# ARM_PCB.net
KiCad netlist of a schematic drawn in Altium Designer
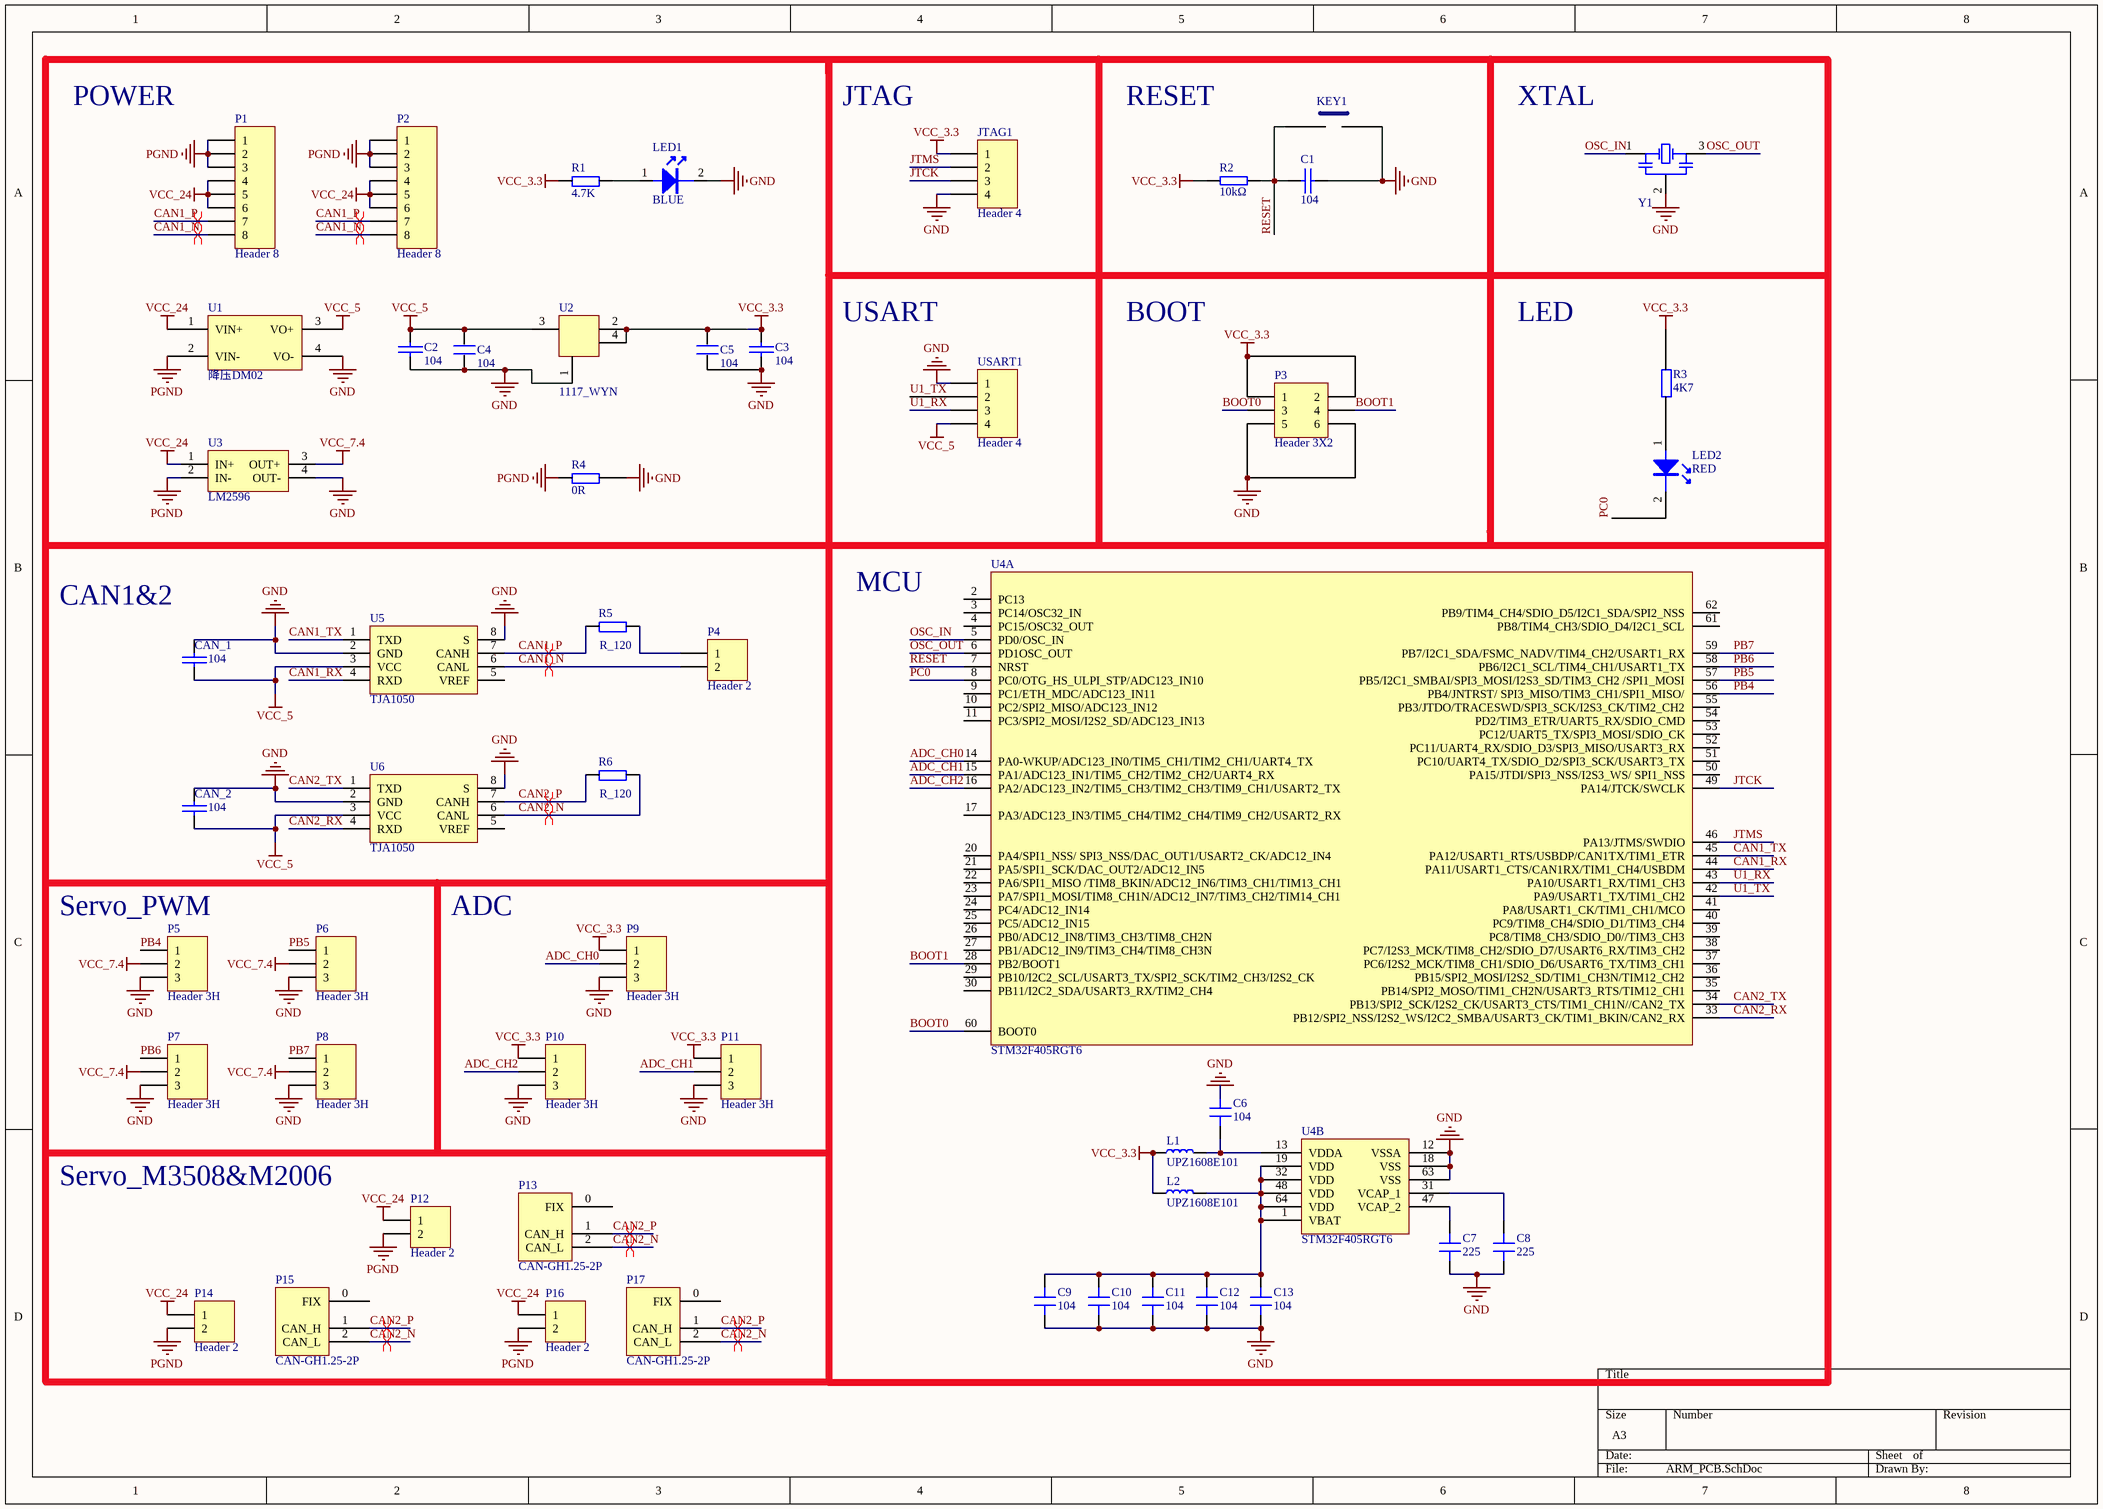
[diagram p0: ARM_PCB.SchDoc]

(export (version "E")
  (design (tool "Eeschema 10.0.6"))
  (components
    (comp (ref "C1") (value "104") (footprint "C0603") (libsource (lib "main") (part "C0603")))
    (comp (ref "C2") (value "104") (footprint "C0603") (libsource (lib "main") (part "C0603")))
    (comp (ref "C3") (value "104") (footprint "C0603") (libsource (lib "main") (part "C0603")))
    (comp (ref "C4") (value "104") (footprint "C0603") (libsource (lib "Rescue") (part "Cap")))
    (comp (ref "C5") (value "104") (footprint "C0603") (libsource (lib "Rescue") (part "Cap")))
    (comp (ref "C6")
      (value "104")
      (footprint "C0603/1608")
      (description "陶瓷电容")
      (libsource (lib "WMJ2019_Devices") (part "陶瓷电容"))
    )
    (comp (ref "C7")
      (value "225")
      (footprint "C0603/1608")
      (description "陶瓷电容")
      (libsource (lib "WMJ2019_Devices") (part "陶瓷电容"))
    )
    (comp (ref "C8")
      (value "225")
      (footprint "C0603/1608")
      (description "陶瓷电容")
      (libsource (lib "WMJ2019_Devices") (part "陶瓷电容"))
    )
    (comp (ref "C9")
      (value "104")
      (footprint "C0603/1608")
      (description "陶瓷电容")
      (libsource (lib "WMJ2019_Devices") (part "陶瓷电容"))
    )
    (comp (ref "C10")
      (value "104")
      (footprint "C0603/1608")
      (description "陶瓷电容")
      (libsource (lib "WMJ2019_Devices") (part "陶瓷电容"))
    )
    (comp (ref "C11")
      (value "104")
      (footprint "C0603/1608")
      (description "陶瓷电容")
      (libsource (lib "WMJ2019_Devices") (part "陶瓷电容"))
    )
    (comp (ref "C12")
      (value "104")
      (footprint "C0603/1608")
      (description "陶瓷电容")
      (libsource (lib "WMJ2019_Devices") (part "陶瓷电容"))
    )
    (comp (ref "C13")
      (value "104")
      (footprint "C0603/1608")
      (description "陶瓷电容")
      (libsource (lib "WMJ2019_Devices") (part "陶瓷电容"))
    )
    (comp (ref "CAN_1") (value "104") (footprint "C0603") (libsource (lib "STM32主处理板") (part "C0603")))
    (comp (ref "CAN_2") (value "104") (footprint "C0603") (libsource (lib "STM32主处理板") (part "C0603")))
    (comp (ref "JTAG1")
      (value "Header 4")
      (footprint "Header1*4_XH2.54_zhi")
      (description "Header, 4-Pin")
      (fields (field (name "PUBLISHER") "Altium Limited"))
      (libsource (lib "Miscellaneous Connectors") (part "Header 4"))
    )
    (comp (ref "KEY1") (value "KEY2") (footprint "KEY_RESET") (libsource (lib "library-1") (part "KEY")))
    (comp (ref "L1")
      (value "UPZ1608E101")
      (footprint "L0603/1608")
      (description "贴片磁珠")
      (libsource (lib "WMJ2019_Devices") (part "磁珠"))
    )
    (comp (ref "L2")
      (value "UPZ1608E101")
      (footprint "L0603/1608")
      (description "贴片磁珠")
      (libsource (lib "WMJ2019_Devices") (part "磁珠"))
    )
    (comp (ref "LED1")
      (value "LED BLUE")
      (footprint "LED0603")
      (fields (field (name "COLOR") "BLUE"))
      (libsource (lib "Rescue") (part "LED"))
    )
    (comp (ref "LED2")
      (value "LED RED")
      (footprint "LED0603")
      (fields (field (name "COLOR") "RED"))
      (libsource (lib "Rescue") (part "LED"))
    )
    (comp (ref "P1")
      (value "Header 8")
      (footprint "Header1*8_XH2.54_zhi")
      (description "Header, 8-Pin")
      (fields (field (name "PUBLISHER") "Altium Limited"))
      (libsource (lib "Miscellaneous Connectors") (part "Header 8"))
    )
    (comp (ref "P2")
      (value "Header 8")
      (footprint "Header1*8_XH2.54_zhi")
      (description "Header, 8-Pin")
      (fields (field (name "PUBLISHER") "Altium Limited"))
      (libsource (lib "Miscellaneous Connectors") (part "Header 8"))
    )
    (comp (ref "P3")
      (value "Header 3X2")
      (footprint "BOOT")
      (description "Header, 3-Pin, Dual row")
      (fields (field (name "PUBLISHER") "Altium Limited"))
      (libsource (lib "PCB_Project") (part "Header 3X2"))
    )
    (comp (ref "P4") (value "Header 2") (footprint "TM") (libsource (lib "Rescue") (part "Header 2")))
    (comp (ref "P5")
      (value "Header 3H")
      (footprint "Header1*3XH2.54")
      (libsource (lib "Rescue") (part "Header 3H"))
    )
    (comp (ref "P6")
      (value "Header 3H")
      (footprint "Header1*3XH2.54")
      (libsource (lib "Rescue") (part "Header 3H"))
    )
    (comp (ref "P7")
      (value "Header 3H")
      (footprint "Header1*3XH2.54")
      (libsource (lib "Rescue") (part "Header 3H"))
    )
    (comp (ref "P8")
      (value "Header 3H")
      (footprint "Header1*3XH2.54")
      (libsource (lib "Rescue") (part "Header 3H"))
    )
    (comp (ref "P9")
      (value "Header 3H")
      (footprint "Header1*3XH2.54")
      (libsource (lib "Rescue") (part "Header 3H"))
    )
    (comp (ref "P10")
      (value "Header 3H")
      (footprint "Header1*3XH2.54")
      (libsource (lib "Rescue") (part "Header 3H"))
    )
    (comp (ref "P11")
      (value "Header 3H")
      (footprint "Header1*3XH2.54")
      (libsource (lib "Rescue") (part "Header 3H"))
    )
    (comp (ref "P12") (value "Header 2") (footprint "XT30_母") (libsource (lib "Rescue") (part "Header 2")))
    (comp (ref "P13")
      (value "CAN-GH1.25-2P")
      (footprint "GH1.25-2P（立式）")
      (description "CAN-GH1.25-2P端子座")
      (libsource (lib "PCB_Project1") (part "CAN-GH1.25-2P"))
    )
    (comp (ref "P14") (value "Header 2") (footprint "XT30_母") (libsource (lib "Rescue") (part "Header 2")))
    (comp (ref "P15")
      (value "CAN-GH1.25-2P")
      (footprint "GH1.25-2P（立式）")
      (description "CAN-GH1.25-2P端子座")
      (libsource (lib "PCB_Project1") (part "CAN-GH1.25-2P"))
    )
    (comp (ref "P16") (value "Header 2") (footprint "XT30_母") (libsource (lib "Rescue") (part "Header 2")))
    (comp (ref "P17")
      (value "CAN-GH1.25-2P")
      (footprint "GH1.25-2P（立式）")
      (description "CAN-GH1.25-2P端子座")
      (libsource (lib "PCB_Project1") (part "CAN-GH1.25-2P"))
    )
    (comp (ref "R1") (value "4.7K") (footprint "R0603") (libsource (lib "战舰STM32开发板底板封装库") (part "R")))
    (comp (ref "R2") (value "10kΩ") (footprint "R0603") (libsource (lib "main") (part "RES_WYN")))
    (comp (ref "R3") (value "4K7") (footprint "R0603") (libsource (lib "Rescue") (part "Resistor")))
    (comp (ref "R4") (value "0R") (footprint "R0603") (libsource (lib "Rescue") (part "Resistor")))
    (comp (ref "R5") (value "R_120") (footprint "R0603") (libsource (lib "战舰STM32开发板底板封装库") (part "R")))
    (comp (ref "R6") (value "R_120") (footprint "R0603") (libsource (lib "战舰STM32开发板底板封装库") (part "R")))
    (comp (ref "U1") (value "降压DM02") (footprint "降压DM02") (libsource (lib "Rescue") (part "降压DM02")))
    (comp (ref "U2") (value "1117_WYN") (footprint "SOT-223") (libsource (lib "STM32主处理板") (part "1117_WYN")))
    (comp (ref "U3")
      (value "LM2596")
      (footprint "LM2596_big")
      (description "云辉 LM2596S DC-DC降压电源模块")
      (libsource (lib "舞蹈常用原理图库") (part "DC-DC稳压模块"))
    )
    (comp (ref "U4")
      (value "STM32F405RGT6")
      (footprint "LQFP64")
      (description "微控制器STM32F405RGT6")
      (libsource (lib "WMJ2019_MCU") (part "STM32F405RGT6"))
    )
    (comp (ref "U5") (value "TJA1050") (footprint "SO8_M") (libsource (lib "Rescue") (part "TJA1050")))
    (comp (ref "U6") (value "TJA1050") (footprint "SO8_M") (libsource (lib "Rescue") (part "TJA1050")))
    (comp (ref "USART1")
      (value "Header 4")
      (footprint "Header1*4_XH2.54_zhi")
      (description "Header, 4-Pin")
      (fields (field (name "PUBLISHER") "Altium Limited"))
      (libsource (lib "Miscellaneous Connectors") (part "Header 4"))
    )
    (comp (ref "Y1")
      (value "Crystal_Cap")
      (footprint "XTAL-3213")
      (fields (field (name "PUBLISHER") "Altium Limited"))
      (libsource (lib "chassis_PCB_Project") (part "Crystal_Cap"))
    )
  )
  (nets
    (net (code "1") (name "/ADC_CH0") (class "Default")
      (node (ref "P9") (pin "2") (pinfunction "2_2") (pintype "passive"))
      (node (ref "U4") (pin "14") (pinfunction "PA0-WKUP/ADC123_IN0/TIM5_CH1/TIM2_CH1/UART4_TX_14") (pintype "passive"))
    )
    (net (code "2") (name "/ADC_CH1") (class "Default")
      (node (ref "P11") (pin "2") (pinfunction "2_2") (pintype "passive"))
      (node (ref "U4") (pin "15") (pinfunction "PA1/ADC123_IN1/TIM5_CH2/TIM2_CH2/UART4_RX_15") (pintype "passive"))
    )
    (net (code "3") (name "/ADC_CH2") (class "Default")
      (node (ref "P10") (pin "2") (pinfunction "2_2") (pintype "passive"))
      (node (ref "U4") (pin "16") (pinfunction "PA2/ADC123_IN2/TIM5_CH3/TIM2_CH3/TIM9_CH1/USART2_TX_16") (pintype "passive"))
    )
    (net (code "4") (name "/BOOT0") (class "Default")
      (node (ref "P3") (pin "3") (pinfunction "3_3") (pintype "passive"))
      (node (ref "U4") (pin "60") (pinfunction "BOOT0_60") (pintype "passive"))
    )
    (net (code "5") (name "/BOOT1") (class "Default")
      (node (ref "P3") (pin "4") (pinfunction "4_4") (pintype "passive"))
      (node (ref "U4") (pin "28") (pinfunction "PB2/BOOT1_28") (pintype "passive"))
    )
    (net (code "6") (name "/CAN1_N") (class "Default")
      (node (ref "P1") (pin "8") (pinfunction "8_8") (pintype "passive"))
      (node (ref "P2") (pin "8") (pinfunction "8_8") (pintype "passive"))
      (node (ref "P4") (pin "2") (pinfunction "2_2") (pintype "passive"))
      (node (ref "U5") (pin "6") (pinfunction "CANL_6") (pintype "passive"))
    )
    (net (code "7") (name "/CAN1_P") (class "Default")
      (node (ref "P1") (pin "7") (pinfunction "7_7") (pintype "passive"))
      (node (ref "P2") (pin "7") (pinfunction "7_7") (pintype "passive"))
      (node (ref "R5") (pin "1") (pintype "passive"))
      (node (ref "U5") (pin "7") (pinfunction "CANH_7") (pintype "passive"))
    )
    (net (code "8") (name "/CAN1_RX") (class "Default")
      (node (ref "U4") (pin "44") (pinfunction "PA11/USART1_CTS/CAN1RX/TIM1_CH4/USBDM_44") (pintype "passive"))
      (node (ref "U5") (pin "4") (pinfunction "RXD_4") (pintype "passive"))
    )
    (net (code "9") (name "/CAN1_TX") (class "Default")
      (node (ref "U4") (pin "45") (pinfunction "PA12/USART1_RTS/USBDP/CAN1TX/TIM1_ETR_45") (pintype "passive"))
      (node (ref "U5") (pin "1") (pinfunction "TXD_1") (pintype "passive"))
    )
    (net (code "10") (name "/CAN2_N") (class "Default")
      (node (ref "P13") (pin "2") (pinfunction "CAN_L_2") (pintype "passive"))
      (node (ref "P15") (pin "2") (pinfunction "CAN_L_2") (pintype "passive"))
      (node (ref "P17") (pin "2") (pinfunction "CAN_L_2") (pintype "passive"))
      (node (ref "R6") (pin "2") (pintype "passive"))
      (node (ref "U6") (pin "6") (pinfunction "CANL_6") (pintype "passive"))
    )
    (net (code "11") (name "/CAN2_P") (class "Default")
      (node (ref "P13") (pin "1") (pinfunction "CAN_H_1") (pintype "passive"))
      (node (ref "P15") (pin "1") (pinfunction "CAN_H_1") (pintype "passive"))
      (node (ref "P17") (pin "1") (pinfunction "CAN_H_1") (pintype "passive"))
      (node (ref "R6") (pin "1") (pintype "passive"))
      (node (ref "U6") (pin "7") (pinfunction "CANH_7") (pintype "passive"))
    )
    (net (code "12") (name "/CAN2_RX") (class "Default")
      (node (ref "U4") (pin "33") (pinfunction "PB12/SPI2_NSS/I2S2_WS/I2C2_SMBA/USART3_CK/TIM1_BKIN/CAN2_RX_33") (pintype "passive"))
      (node (ref "U6") (pin "4") (pinfunction "RXD_4") (pintype "passive"))
    )
    (net (code "13") (name "/CAN2_TX") (class "Default")
      (node (ref "U4") (pin "34") (pinfunction "PB13/SPI2_SCK/I2S2_CK/USART3_CTS/TIM1_CH1N//CAN2_TX_34") (pintype "passive"))
      (node (ref "U6") (pin "1") (pinfunction "TXD_1") (pintype "passive"))
    )
    (net (code "14") (name "/JTCK") (class "Default")
      (node (ref "JTAG1") (pin "3") (pinfunction "3_3") (pintype "passive"))
      (node (ref "U4") (pin "49") (pinfunction "PA14/JTCK/SWCLK_49") (pintype "passive"))
    )
    (net (code "15") (name "/JTMS") (class "Default")
      (node (ref "JTAG1") (pin "2") (pinfunction "2_2") (pintype "passive"))
      (node (ref "U4") (pin "46") (pinfunction "PA13/JTMS/SWDIO_46") (pintype "passive"))
    )
    (net (code "16") (name "/OSC_IN") (class "Default")
      (node (ref "U4") (pin "5") (pinfunction "PD0/OSC_IN_5") (pintype "passive"))
      (node (ref "Y1") (pin "1") (pinfunction "OSC1_1") (pintype "passive"))
    )
    (net (code "17") (name "/OSC_OUT") (class "Default")
      (node (ref "U4") (pin "6") (pinfunction "PD1OSC_OUT_6") (pintype "passive"))
      (node (ref "Y1") (pin "3") (pinfunction "OSC3_3") (pintype "passive"))
    )
    (net (code "18") (name "/PB4") (class "Default")
      (node (ref "P5") (pin "1") (pinfunction "1_1") (pintype "passive"))
      (node (ref "U4") (pin "56") (pinfunction "PB4/JNTRST/_SPI3_MISO/TIM3_CH1/SPI1_MISO/_56") (pintype "passive"))
    )
    (net (code "19") (name "/PB5") (class "Default")
      (node (ref "P6") (pin "1") (pinfunction "1_1") (pintype "passive"))
      (node (ref "U4") (pin "57") (pinfunction "PB5/I2C1_SMBAI/SPI3_MOSI/I2S3_SD/TIM3_CH2_/SPI1_MOSI_57") (pintype "passive"))
    )
    (net (code "20") (name "/PB6") (class "Default")
      (node (ref "P7") (pin "1") (pinfunction "1_1") (pintype "passive"))
      (node (ref "U4") (pin "58") (pinfunction "PB6/I2C1_SCL/TIM4_CH1/USART1_TX_58") (pintype "passive"))
    )
    (net (code "21") (name "/PB7") (class "Default")
      (node (ref "P8") (pin "1") (pinfunction "1_1") (pintype "passive"))
      (node (ref "U4") (pin "59") (pinfunction "PB7/I2C1_SDA/FSMC_NADV/TIM4_CH2/USART1_RX_59") (pintype "passive"))
    )
    (net (code "22") (name "/PC0") (class "Default")
      (node (ref "LED2") (pin "2") (pinfunction "K_2") (pintype "passive"))
      (node (ref "U4") (pin "8") (pinfunction "PC0/OTG_HS_ULPI_STP/ADC123_IN10_8") (pintype "passive"))
    )
    (net (code "23") (name "/RESET") (class "Default")
      (node (ref "C1") (pin "1") (pintype "passive"))
      (node (ref "KEY1") (pin "2") (pinfunction "2_2") (pintype "passive"))
      (node (ref "R2") (pin "1") (pinfunction "1_1") (pintype "passive"))
      (node (ref "U4") (pin "7") (pinfunction "NRST_7") (pintype "passive"))
    )
    (net (code "24") (name "/U1_RX") (class "Default")
      (node (ref "U4") (pin "43") (pinfunction "PA10/USART1_RX/TIM1_CH3_43") (pintype "passive"))
      (node (ref "USART1") (pin "3") (pinfunction "3_3") (pintype "passive"))
    )
    (net (code "25") (name "/U1_TX") (class "Default")
      (node (ref "U4") (pin "42") (pinfunction "PA9/USART1_TX/TIM1_CH2_42") (pintype "passive"))
      (node (ref "USART1") (pin "2") (pinfunction "2_2") (pintype "passive"))
    )
    (net (code "26") (name "GND") (class "Default")
      (node (ref "C1") (pin "2") (pintype "passive"))
      (node (ref "C10") (pin "1") (pintype "passive"))
      (node (ref "C11") (pin "1") (pintype "passive"))
      (node (ref "C12") (pin "1") (pintype "passive"))
      (node (ref "C13") (pin "1") (pintype "passive"))
      (node (ref "C2") (pin "2") (pintype "passive"))
      (node (ref "C3") (pin "2") (pintype "passive"))
      (node (ref "C4") (pin "1") (pintype "passive"))
      (node (ref "C5") (pin "1") (pintype "passive"))
      (node (ref "C6") (pin "2") (pintype "passive"))
      (node (ref "C7") (pin "1") (pintype "passive"))
      (node (ref "C8") (pin "1") (pintype "passive"))
      (node (ref "C9") (pin "1") (pintype "passive"))
      (node (ref "CAN_1") (pin "1") (pintype "passive"))
      (node (ref "CAN_2") (pin "1") (pintype "passive"))
      (node (ref "JTAG1") (pin "4") (pinfunction "4_4") (pintype "passive"))
      (node (ref "KEY1") (pin "1") (pinfunction "1_1") (pintype "passive"))
      (node (ref "LED1") (pin "2") (pinfunction "K_2") (pintype "passive"))
      (node (ref "P10") (pin "3") (pinfunction "3_3") (pintype "passive"))
      (node (ref "P11") (pin "3") (pinfunction "3_3") (pintype "passive"))
      (node (ref "P3") (pin "5") (pinfunction "5_5") (pintype "passive"))
      (node (ref "P3") (pin "6") (pinfunction "6_6") (pintype "passive"))
      (node (ref "P5") (pin "3") (pinfunction "3_3") (pintype "passive"))
      (node (ref "P6") (pin "3") (pinfunction "3_3") (pintype "passive"))
      (node (ref "P7") (pin "3") (pinfunction "3_3") (pintype "passive"))
      (node (ref "P8") (pin "3") (pinfunction "3_3") (pintype "passive"))
      (node (ref "P9") (pin "3") (pinfunction "3_3") (pintype "passive"))
      (node (ref "R4") (pin "2") (pintype "passive"))
      (node (ref "U1") (pin "4") (pinfunction "VO-_4") (pintype "passive"))
      (node (ref "U2") (pin "1") (pintype "passive"))
      (node (ref "U3") (pin "4") (pinfunction "OUT-_4") (pintype "passive"))
      (node (ref "U4") (pin "12") (pinfunction "VSSA_12") (pintype "passive"))
      (node (ref "U4") (pin "18") (pinfunction "VSS_18") (pintype "passive"))
      (node (ref "U4") (pin "63") (pinfunction "VSS_63") (pintype "passive"))
      (node (ref "U5") (pin "2") (pinfunction "GND_2") (pintype "passive"))
      (node (ref "U5") (pin "8") (pinfunction "S_8") (pintype "passive"))
      (node (ref "U6") (pin "2") (pinfunction "GND_2") (pintype "passive"))
      (node (ref "U6") (pin "8") (pinfunction "S_8") (pintype "passive"))
      (node (ref "USART1") (pin "1") (pinfunction "1_1") (pintype "passive"))
      (node (ref "Y1") (pin "2") (pinfunction "OSC2_2") (pintype "passive"))
    )
    (net (code "27") (name "Net-(LED1-A)") (class "Default")
      (node (ref "LED1") (pin "1") (pinfunction "A_1") (pintype "passive"))
      (node (ref "R1") (pin "2") (pintype "passive"))
    )
    (net (code "28") (name "Net-(LED2-A)") (class "Default")
      (node (ref "LED2") (pin "1") (pinfunction "A_1") (pintype "passive"))
      (node (ref "R3") (pin "1") (pintype "passive"))
    )
    (net (code "29") (name "Net-(P4-Pad1)") (class "Default")
      (node (ref "P4") (pin "1") (pinfunction "1_1") (pintype "passive"))
      (node (ref "R5") (pin "2") (pintype "passive"))
    )
    (net (code "30") (name "Net-(U4B-VBAT)") (class "Default")
      (node (ref "C10") (pin "2") (pintype "passive"))
      (node (ref "C11") (pin "2") (pintype "passive"))
      (node (ref "C12") (pin "2") (pintype "passive"))
      (node (ref "C13") (pin "2") (pintype "passive"))
      (node (ref "C9") (pin "2") (pintype "passive"))
      (node (ref "L2") (pin "2") (pinfunction "2_2") (pintype "passive"))
      (node (ref "U4") (pin "1") (pinfunction "VBAT_1") (pintype "passive"))
      (node (ref "U4") (pin "19") (pinfunction "VDD_19") (pintype "passive"))
      (node (ref "U4") (pin "32") (pinfunction "VDD_32") (pintype "passive"))
      (node (ref "U4") (pin "48") (pinfunction "VDD_48") (pintype "passive"))
      (node (ref "U4") (pin "64") (pinfunction "VDD_64") (pintype "passive"))
    )
    (net (code "31") (name "Net-(U4B-VCAP_1)") (class "Default")
      (node (ref "C8") (pin "2") (pintype "passive"))
      (node (ref "U4") (pin "31") (pinfunction "VCAP_1_31") (pintype "passive"))
    )
    (net (code "32") (name "Net-(U4B-VCAP_2)") (class "Default")
      (node (ref "C7") (pin "2") (pintype "passive"))
      (node (ref "U4") (pin "47") (pinfunction "VCAP_2_47") (pintype "passive"))
    )
    (net (code "33") (name "Net-(U4B-VDDA)") (class "Default")
      (node (ref "C6") (pin "1") (pintype "passive"))
      (node (ref "L1") (pin "2") (pinfunction "2_2") (pintype "passive"))
      (node (ref "U4") (pin "13") (pinfunction "VDDA_13") (pintype "passive"))
    )
    (net (code "34") (name "PGND") (class "Default")
      (node (ref "P1") (pin "1") (pinfunction "1_1") (pintype "passive"))
      (node (ref "P1") (pin "2") (pinfunction "2_2") (pintype "passive"))
      (node (ref "P1") (pin "3") (pinfunction "3_3") (pintype "passive"))
      (node (ref "P12") (pin "2") (pinfunction "2_2") (pintype "passive"))
      (node (ref "P14") (pin "2") (pinfunction "2_2") (pintype "passive"))
      (node (ref "P16") (pin "2") (pinfunction "2_2") (pintype "passive"))
      (node (ref "P2") (pin "1") (pinfunction "1_1") (pintype "passive"))
      (node (ref "P2") (pin "2") (pinfunction "2_2") (pintype "passive"))
      (node (ref "P2") (pin "3") (pinfunction "3_3") (pintype "passive"))
      (node (ref "R4") (pin "1") (pintype "passive"))
      (node (ref "U1") (pin "2") (pinfunction "VIN-_2") (pintype "passive"))
      (node (ref "U3") (pin "2") (pinfunction "IN-_2") (pintype "passive"))
    )
    (net (code "35") (name "VCC_3.3") (class "Default")
      (node (ref "C3") (pin "1") (pintype "passive"))
      (node (ref "C5") (pin "2") (pintype "passive"))
      (node (ref "JTAG1") (pin "1") (pinfunction "1_1") (pintype "passive"))
      (node (ref "L1") (pin "1") (pinfunction "1_1") (pintype "passive"))
      (node (ref "L2") (pin "1") (pinfunction "1_1") (pintype "passive"))
      (node (ref "P10") (pin "1") (pinfunction "1_1") (pintype "passive"))
      (node (ref "P11") (pin "1") (pinfunction "1_1") (pintype "passive"))
      (node (ref "P3") (pin "1") (pinfunction "1_1") (pintype "passive"))
      (node (ref "P3") (pin "2") (pinfunction "2_2") (pintype "passive"))
      (node (ref "P9") (pin "1") (pinfunction "1_1") (pintype "passive"))
      (node (ref "R1") (pin "1") (pintype "passive"))
      (node (ref "R2") (pin "2") (pinfunction "2_2") (pintype "passive"))
      (node (ref "R3") (pin "2") (pintype "passive"))
      (node (ref "U2") (pin "2") (pintype "passive"))
      (node (ref "U2") (pin "4") (pintype "passive"))
    )
    (net (code "36") (name "VCC_5") (class "Default")
      (node (ref "C2") (pin "1") (pintype "passive"))
      (node (ref "C4") (pin "2") (pintype "passive"))
      (node (ref "CAN_1") (pin "2") (pintype "passive"))
      (node (ref "CAN_2") (pin "2") (pintype "passive"))
      (node (ref "U1") (pin "3") (pinfunction "VO+_3") (pintype "passive"))
      (node (ref "U2") (pin "3") (pintype "passive"))
      (node (ref "U5") (pin "3") (pinfunction "VCC_3") (pintype "passive"))
      (node (ref "U6") (pin "3") (pinfunction "VCC_3") (pintype "passive"))
      (node (ref "USART1") (pin "4") (pinfunction "4_4") (pintype "passive"))
    )
    (net (code "37") (name "VCC_7.4") (class "Default")
      (node (ref "P5") (pin "2") (pinfunction "2_2") (pintype "passive"))
      (node (ref "P6") (pin "2") (pinfunction "2_2") (pintype "passive"))
      (node (ref "P7") (pin "2") (pinfunction "2_2") (pintype "passive"))
      (node (ref "P8") (pin "2") (pinfunction "2_2") (pintype "passive"))
      (node (ref "U3") (pin "3") (pinfunction "OUT+_3") (pintype "passive"))
    )
    (net (code "38") (name "VCC_24") (class "Default")
      (node (ref "P1") (pin "4") (pinfunction "4_4") (pintype "passive"))
      (node (ref "P1") (pin "5") (pinfunction "5_5") (pintype "passive"))
      (node (ref "P1") (pin "6") (pinfunction "6_6") (pintype "passive"))
      (node (ref "P12") (pin "1") (pinfunction "1_1") (pintype "passive"))
      (node (ref "P14") (pin "1") (pinfunction "1_1") (pintype "passive"))
      (node (ref "P16") (pin "1") (pinfunction "1_1") (pintype "passive"))
      (node (ref "P2") (pin "4") (pinfunction "4_4") (pintype "passive"))
      (node (ref "P2") (pin "5") (pinfunction "5_5") (pintype "passive"))
      (node (ref "P2") (pin "6") (pinfunction "6_6") (pintype "passive"))
      (node (ref "U1") (pin "1") (pinfunction "VIN+_1") (pintype "passive"))
      (node (ref "U3") (pin "1") (pinfunction "IN+_1") (pintype "passive"))
    )
    (net (code "39") (name "unconnected-(P13-FIX-Pad0)") (class "Default")
      (node (ref "P13") (pin "0") (pinfunction "FIX_0") (pintype "passive"))
    )
    (net (code "40") (name "unconnected-(P15-FIX-Pad0)") (class "Default")
      (node (ref "P15") (pin "0") (pinfunction "FIX_0") (pintype "passive"))
    )
    (net (code "41") (name "unconnected-(P17-FIX-Pad0)") (class "Default")
      (node (ref "P17") (pin "0") (pinfunction "FIX_0") (pintype "passive"))
    )
    (net (code "42") (name "unconnected-(U4A-PA3{slash}ADC123_IN3{slash}TIM5_CH4{slash}TIM2_CH4{slash}TIM9_CH2{slash}USART2_RX-Pad17)") (class "Default")
      (node (ref "U4") (pin "17") (pinfunction "PA3/ADC123_IN3/TIM5_CH4/TIM2_CH4/TIM9_CH2/USART2_RX_17") (pintype "passive"))
    )
    (net (code "43") (name "unconnected-(U4A-PA4{slash}SPI1_NSS{slash}_SPI3_NSS{slash}DAC_OUT1{slash}USART2_CK{slash}ADC12_IN4-Pad20)") (class "Default")
      (node (ref "U4") (pin "20") (pinfunction "PA4/SPI1_NSS/_SPI3_NSS/DAC_OUT1/USART2_CK/ADC12_IN4_20") (pintype "passive"))
    )
    (net (code "44") (name "unconnected-(U4A-PA5{slash}SPI1_SCK{slash}DAC_OUT2{slash}ADC12_IN5-Pad21)") (class "Default")
      (node (ref "U4") (pin "21") (pinfunction "PA5/SPI1_SCK/DAC_OUT2/ADC12_IN5_21") (pintype "passive"))
    )
    (net (code "45") (name "unconnected-(U4A-PA6{slash}SPI1_MISO_{slash}TIM8_BKIN{slash}ADC12_IN6{slash}TIM3_CH1{slash}TIM13_CH1-Pad22)") (class "Default")
      (node (ref "U4") (pin "22") (pinfunction "PA6/SPI1_MISO_/TIM8_BKIN/ADC12_IN6/TIM3_CH1/TIM13_CH1_22") (pintype "passive"))
    )
    (net (code "46") (name "unconnected-(U4A-PA7{slash}SPI1_MOSI{slash}TIM8_CH1N{slash}ADC12_IN7{slash}TIM3_CH2{slash}TIM14_CH1-Pad23)") (class "Default")
      (node (ref "U4") (pin "23") (pinfunction "PA7/SPI1_MOSI/TIM8_CH1N/ADC12_IN7/TIM3_CH2/TIM14_CH1_23") (pintype "passive"))
    )
    (net (code "47") (name "unconnected-(U4A-PA8{slash}USART1_CK{slash}TIM1_CH1{slash}MCO-Pad41)") (class "Default")
      (node (ref "U4") (pin "41") (pinfunction "PA8/USART1_CK/TIM1_CH1/MCO_41") (pintype "passive"))
    )
    (net (code "48") (name "unconnected-(U4A-PA15{slash}JTDI{slash}SPI3_NSS{slash}I2S3_WS{slash}_SPI1_NSS-Pad50)") (class "Default")
      (node (ref "U4") (pin "50") (pinfunction "PA15/JTDI/SPI3_NSS/I2S3_WS/_SPI1_NSS_50") (pintype "passive"))
    )
    (net (code "49") (name "unconnected-(U4A-PB0{slash}ADC12_IN8{slash}TIM3_CH3{slash}TIM8_CH2N-Pad26)") (class "Default")
      (node (ref "U4") (pin "26") (pinfunction "PB0/ADC12_IN8/TIM3_CH3/TIM8_CH2N_26") (pintype "passive"))
    )
    (net (code "50") (name "unconnected-(U4A-PB1{slash}ADC12_IN9{slash}TIM3_CH4{slash}TIM8_CH3N-Pad27)") (class "Default")
      (node (ref "U4") (pin "27") (pinfunction "PB1/ADC12_IN9/TIM3_CH4/TIM8_CH3N_27") (pintype "passive"))
    )
    (net (code "51") (name "unconnected-(U4A-PB3{slash}JTDO{slash}TRACESWD{slash}SPI3_SCK{slash}I2S3_CK{slash}TIM2_CH2-Pad55)") (class "Default")
      (node (ref "U4") (pin "55") (pinfunction "PB3/JTDO/TRACESWD/SPI3_SCK/I2S3_CK/TIM2_CH2_55") (pintype "passive"))
    )
    (net (code "52") (name "unconnected-(U4A-PB8{slash}TIM4_CH3{slash}SDIO_D4{slash}I2C1_SCL-Pad61)") (class "Default")
      (node (ref "U4") (pin "61") (pinfunction "PB8/TIM4_CH3/SDIO_D4/I2C1_SCL_61") (pintype "passive"))
    )
    (net (code "53") (name "unconnected-(U4A-PB9{slash}TIM4_CH4{slash}SDIO_D5{slash}I2C1_SDA{slash}SPI2_NSS-Pad62)") (class "Default")
      (node (ref "U4") (pin "62") (pinfunction "PB9/TIM4_CH4/SDIO_D5/I2C1_SDA/SPI2_NSS_62") (pintype "passive"))
    )
    (net (code "54") (name "unconnected-(U4A-PB10{slash}I2C2_SCL{slash}USART3_TX{slash}SPI2_SCK{slash}TIM2_CH3{slash}I2S2_CK-Pad29)") (class "Default")
      (node (ref "U4") (pin "29") (pinfunction "PB10/I2C2_SCL/USART3_TX/SPI2_SCK/TIM2_CH3/I2S2_CK_29") (pintype "passive"))
    )
    (net (code "55") (name "unconnected-(U4A-PB11{slash}I2C2_SDA{slash}USART3_RX{slash}TIM2_CH4-Pad30)") (class "Default")
      (node (ref "U4") (pin "30") (pinfunction "PB11/I2C2_SDA/USART3_RX/TIM2_CH4_30") (pintype "passive"))
    )
    (net (code "56") (name "unconnected-(U4A-PB14{slash}SPI2_MOSO{slash}TIM1_CH2N{slash}USART3_RTS{slash}TIM12_CH1-Pad35)") (class "Default")
      (node (ref "U4") (pin "35") (pinfunction "PB14/SPI2_MOSO/TIM1_CH2N/USART3_RTS/TIM12_CH1_35") (pintype "passive"))
    )
    (net (code "57") (name "unconnected-(U4A-PB15{slash}SPI2_MOSI{slash}I2S2_SD{slash}TIM1_CH3N{slash}TIM12_CH2-Pad36)") (class "Default")
      (node (ref "U4") (pin "36") (pinfunction "PB15/SPI2_MOSI/I2S2_SD/TIM1_CH3N/TIM12_CH2_36") (pintype "passive"))
    )
    (net (code "58") (name "unconnected-(U4A-PC1{slash}ETH_MDC{slash}ADC123_IN11-Pad9)") (class "Default")
      (node (ref "U4") (pin "9") (pinfunction "PC1/ETH_MDC/ADC123_IN11_9") (pintype "passive"))
    )
    (net (code "59") (name "unconnected-(U4A-PC2{slash}SPI2_MISO{slash}ADC123_IN12-Pad10)") (class "Default")
      (node (ref "U4") (pin "10") (pinfunction "PC2/SPI2_MISO/ADC123_IN12_10") (pintype "passive"))
    )
    (net (code "60") (name "unconnected-(U4A-PC3{slash}SPI2_MOSI{slash}I2S2_SD{slash}ADC123_IN13-Pad11)") (class "Default")
      (node (ref "U4") (pin "11") (pinfunction "PC3/SPI2_MOSI/I2S2_SD/ADC123_IN13_11") (pintype "passive"))
    )
    (net (code "61") (name "unconnected-(U4A-PC4{slash}ADC12_IN14-Pad24)") (class "Default")
      (node (ref "U4") (pin "24") (pinfunction "PC4/ADC12_IN14_24") (pintype "passive"))
    )
    (net (code "62") (name "unconnected-(U4A-PC5{slash}ADC12_IN15-Pad25)") (class "Default")
      (node (ref "U4") (pin "25") (pinfunction "PC5/ADC12_IN15_25") (pintype "passive"))
    )
    (net (code "63") (name "unconnected-(U4A-PC6{slash}I2S2_MCK{slash}TIM8_CH1{slash}SDIO_D6{slash}USART6_TX{slash}TIM3_CH1-Pad37)") (class "Default")
      (node (ref "U4") (pin "37") (pinfunction "PC6/I2S2_MCK/TIM8_CH1/SDIO_D6/USART6_TX/TIM3_CH1_37") (pintype "passive"))
    )
    (net (code "64") (name "unconnected-(U4A-PC7{slash}I2S3_MCK{slash}TIM8_CH2{slash}SDIO_D7{slash}USART6_RX{slash}TIM3_CH2-Pad38)") (class "Default")
      (node (ref "U4") (pin "38") (pinfunction "PC7/I2S3_MCK/TIM8_CH2/SDIO_D7/USART6_RX/TIM3_CH2_38") (pintype "passive"))
    )
    (net (code "65") (name "unconnected-(U4A-PC8{slash}TIM8_CH3{slash}SDIO_D0{slash}{slash}TIM3_CH3-Pad39)") (class "Default")
      (node (ref "U4") (pin "39") (pinfunction "PC8/TIM8_CH3/SDIO_D0//TIM3_CH3_39") (pintype "passive"))
    )
    (net (code "66") (name "unconnected-(U4A-PC9{slash}TIM8_CH4{slash}SDIO_D1{slash}TIM3_CH4-Pad40)") (class "Default")
      (node (ref "U4") (pin "40") (pinfunction "PC9/TIM8_CH4/SDIO_D1/TIM3_CH4_40") (pintype "passive"))
    )
    (net (code "67") (name "unconnected-(U4A-PC10{slash}UART4_TX{slash}SDIO_D2{slash}SPI3_SCK{slash}USART3_TX-Pad51)") (class "Default")
      (node (ref "U4") (pin "51") (pinfunction "PC10/UART4_TX/SDIO_D2/SPI3_SCK/USART3_TX_51") (pintype "passive"))
    )
    (net (code "68") (name "unconnected-(U4A-PC11{slash}UART4_RX{slash}SDIO_D3{slash}SPI3_MISO{slash}USART3_RX-Pad52)") (class "Default")
      (node (ref "U4") (pin "52") (pinfunction "PC11/UART4_RX/SDIO_D3/SPI3_MISO/USART3_RX_52") (pintype "passive"))
    )
    (net (code "69") (name "unconnected-(U4A-PC12{slash}UART5_TX{slash}SPI3_MOSI{slash}SDIO_CK-Pad53)") (class "Default")
      (node (ref "U4") (pin "53") (pinfunction "PC12/UART5_TX/SPI3_MOSI/SDIO_CK_53") (pintype "passive"))
    )
    (net (code "70") (name "unconnected-(U4A-PC13-Pad2)") (class "Default")
      (node (ref "U4") (pin "2") (pinfunction "PC13_2") (pintype "passive"))
    )
    (net (code "71") (name "unconnected-(U4A-PC14{slash}OSC32_IN-Pad3)") (class "Default")
      (node (ref "U4") (pin "3") (pinfunction "PC14/OSC32_IN_3") (pintype "passive"))
    )
    (net (code "72") (name "unconnected-(U4A-PC15{slash}OSC32_OUT-Pad4)") (class "Default")
      (node (ref "U4") (pin "4") (pinfunction "PC15/OSC32_OUT_4") (pintype "passive"))
    )
    (net (code "73") (name "unconnected-(U4A-PD2{slash}TIM3_ETR{slash}UART5_RX{slash}SDIO_CMD-Pad54)") (class "Default")
      (node (ref "U4") (pin "54") (pinfunction "PD2/TIM3_ETR/UART5_RX/SDIO_CMD_54") (pintype "passive"))
    )
    (net (code "74") (name "unconnected-(U5-VREF-Pad5)") (class "Default")
      (node (ref "U5") (pin "5") (pinfunction "VREF_5") (pintype "passive"))
    )
    (net (code "75") (name "unconnected-(U6-VREF-Pad5)") (class "Default")
      (node (ref "U6") (pin "5") (pinfunction "VREF_5") (pintype "passive"))
    )
  )
)
